# TDS_sensor.net
KiCad netlist of a schematic drawn in Altium Designer
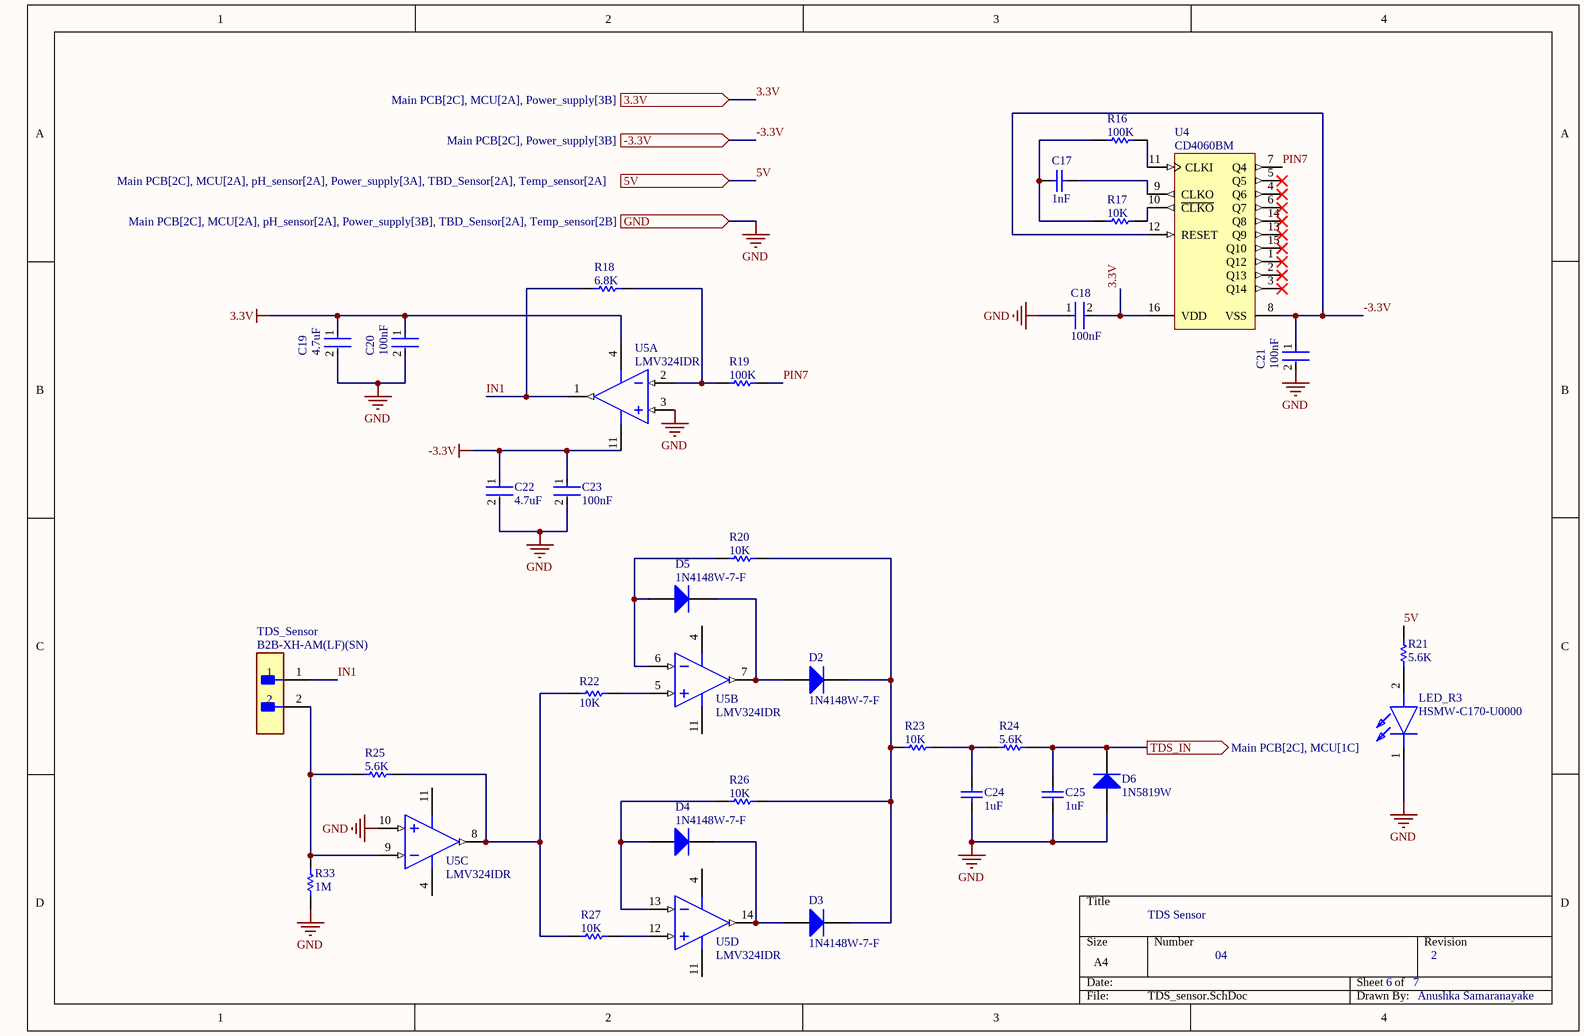
[diagram p0: TDS_sensor.SchDoc]

(export (version "E")
  (design (tool "Eeschema 10.0.6"))
  (components
    (comp (ref "C17")
      (value "1nF")
      (footprint "CAPC2013X135X50LL15T20")
      (fields (field (name "MANUFACTURER") "Vitramon") (field (name "PART NUMBER") "VJ0805Y102KXACW1BC"))
      (libsource (lib "Altium Content Vault") (part "CAP"))
    )
    (comp (ref "C18")
      (value "100nF")
      (footprint "FP-CL31-IPC_B")
      (description "Cap Ceramic 100nF 50V X7R ±10% SMD 1206 +125°C Embossed T/R")
      (fields (field (name "VOLTAGE") "50V") (field (name "TOLERANCE") "10%"))
      (libsource (lib "Altium Content Vault") (part "b4654b650e69147ec39a6b967a45e02"))
    )
    (comp (ref "C19")
      (value "4.7uF")
      (footprint "FP-CL31-IPC_B")
      (description "Cap Ceramic 100nF 50V X7R ±10% SMD 1206 +125°C Embossed T/R")
      (fields (field (name "VOLTAGE") "50V") (field (name "TOLERANCE") "10%"))
      (libsource (lib "Altium Content Vault") (part "b4654b650e69147ec39a6b967a45e02"))
    )
    (comp (ref "C20")
      (value "100nF")
      (footprint "FP-CL31-IPC_B")
      (description "Cap Ceramic 100nF 50V X7R ±10% SMD 1206 +125°C Embossed T/R")
      (fields (field (name "VOLTAGE") "50V") (field (name "TOLERANCE") "10%"))
      (libsource (lib "Altium Content Vault") (part "b4654b650e69147ec39a6b967a45e02"))
    )
    (comp (ref "C21")
      (value "100nF")
      (footprint "FP-CL31-IPC_B")
      (description "Cap Ceramic 100nF 50V X7R ±10% SMD 1206 +125°C Embossed T/R")
      (fields (field (name "VOLTAGE") "50V") (field (name "TOLERANCE") "10%"))
      (libsource (lib "Altium Content Vault") (part "b4654b650e69147ec39a6b967a45e02"))
    )
    (comp (ref "C22")
      (value "4.7uF")
      (footprint "FP-CL31-IPC_B")
      (description "Cap Ceramic 100nF 50V X7R ±10% SMD 1206 +125°C Embossed T/R")
      (fields (field (name "VOLTAGE") "50V") (field (name "TOLERANCE") "10%"))
      (libsource (lib "Altium Content Vault") (part "b4654b650e69147ec39a6b967a45e02"))
    )
    (comp (ref "C23")
      (value "100nF")
      (footprint "FP-CL31-IPC_B")
      (description "Cap Ceramic 100nF 50V X7R ±10% SMD 1206 +125°C Embossed T/R")
      (fields (field (name "VOLTAGE") "50V") (field (name "TOLERANCE") "10%"))
      (libsource (lib "Altium Content Vault") (part "b4654b650e69147ec39a6b967a45e02"))
    )
    (comp (ref "C24")
      (value "1uF")
      (footprint "CAPC2013X135X50LL15T20")
      (fields (field (name "MANUFACTURER") "Vitramon") (field (name "PART NUMBER") "VJ0805Y102KXACW1BC"))
      (libsource (lib "Altium Content Vault") (part "CAP"))
    )
    (comp (ref "C25")
      (value "1uF")
      (footprint "CAPC2013X135X50LL15T20")
      (fields (field (name "MANUFACTURER") "Vitramon") (field (name "PART NUMBER") "VJ0805Y102KXACW1BC"))
      (libsource (lib "Altium Content Vault") (part "CAP"))
    )
    (comp (ref "D2")
      (value "1N4148W-7-F")
      (footprint "DIOD-SOD123-2_V")
      (description "Fast Switching Diode, 100 V, 0.15 A, -65 to 150 degC, 2-Pin?SOD123, RoHS, Tape and Reel")
      (fields (field (name "MANUFACTURER") "DiodesIncorporated"))
      (libsource (lib "Altium Content Vault") (part "D-AK-2"))
    )
    (comp (ref "D3")
      (value "1N4148W-7-F")
      (footprint "DIOD-SOD123-2_V")
      (description "Fast Switching Diode, 100 V, 0.15 A, -65 to 150 degC, 2-Pin?SOD123, RoHS, Tape and Reel")
      (fields (field (name "MANUFACTURER") "DiodesIncorporated"))
      (libsource (lib "Altium Content Vault") (part "D-AK-2"))
    )
    (comp (ref "D4")
      (value "1N4148W-7-F")
      (footprint "DIOD-SOD123-2_V")
      (description "Fast Switching Diode, 100 V, 0.15 A, -65 to 150 degC, 2-Pin?SOD123, RoHS, Tape and Reel")
      (fields (field (name "MANUFACTURER") "DiodesIncorporated"))
      (libsource (lib "Altium Content Vault") (part "D-AK-2"))
    )
    (comp (ref "D5")
      (value "1N4148W-7-F")
      (footprint "DIOD-SOD123-2_V")
      (description "Fast Switching Diode, 100 V, 0.15 A, -65 to 150 degC, 2-Pin?SOD123, RoHS, Tape and Reel")
      (fields (field (name "MANUFACTURER") "DiodesIncorporated"))
      (libsource (lib "Altium Content Vault") (part "D-AK-2"))
    )
    (comp (ref "D6")
      (value "1N5819W")
      (footprint "DIOD-SOD123-2_V")
      (description "Fast Switching Diode, 100 V, 0.15 A, -65 to 150 degC, 2-Pin?SOD123, RoHS, Tape and Reel")
      (fields (field (name "MANUFACTURER") "DiodesIncorporated"))
      (libsource (lib "Altium Content Vault") (part "D-AK-2"))
    )
    (comp (ref "LED_R3")
      (value "HSMW-C170-U0000")
      (footprint "SamacSys:LEDC2012X90N")
      (description "LED")
      (fields (field (name "MOUSER PART NUMBER") "630-HSMW-C170-U0000"))
      (libsource (lib "*") (part "HSMW-C170-U0000"))
    )
    (comp (ref "R16")
      (value "100K")
      (footprint "RESC3216X70X50LL20T25")
      (fields (field (name "MANUFACTURER") "Panasonic") (field (name "PART NUMBER") "ERA8AEB103V"))
      (libsource (lib "Altium Content Vault") (part "RES"))
    )
    (comp (ref "R17")
      (value "10K")
      (footprint "RESC3216X70X50LL20T25")
      (fields (field (name "MANUFACTURER") "Panasonic") (field (name "PART NUMBER") "ERA8AEB103V"))
      (libsource (lib "Altium Content Vault") (part "RES"))
    )
    (comp (ref "R18")
      (value "6.8K")
      (footprint "RESC3216X70X50LL20T25")
      (fields (field (name "MANUFACTURER") "Panasonic") (field (name "PART NUMBER") "ERA8AEB103V"))
      (libsource (lib "Altium Content Vault") (part "RES"))
    )
    (comp (ref "R19")
      (value "100K")
      (footprint "RESC3216X70X50LL20T25")
      (fields (field (name "MANUFACTURER") "Panasonic") (field (name "PART NUMBER") "ERA8AEB103V"))
      (libsource (lib "Altium Content Vault") (part "RES"))
    )
    (comp (ref "R20")
      (value "10K")
      (footprint "RESC3216X70X50LL20T25")
      (fields (field (name "MANUFACTURER") "Panasonic") (field (name "PART NUMBER") "ERA8AEB103V"))
      (libsource (lib "Altium Content Vault") (part "RES"))
    )
    (comp (ref "R21")
      (value "5.6K")
      (footprint "RESC3216X70X50LL20T25")
      (fields (field (name "MANUFACTURER") "Panasonic") (field (name "PART NUMBER") "ERA8AEB103V"))
      (libsource (lib "Altium Content Vault") (part "RES"))
    )
    (comp (ref "R22")
      (value "10K")
      (footprint "RESC3216X70X50LL20T25")
      (fields (field (name "MANUFACTURER") "Panasonic") (field (name "PART NUMBER") "ERA8AEB103V"))
      (libsource (lib "Altium Content Vault") (part "RES"))
    )
    (comp (ref "R23")
      (value "10K")
      (footprint "RESC3216X70X50LL20T25")
      (fields (field (name "MANUFACTURER") "Panasonic") (field (name "PART NUMBER") "ERA8AEB103V"))
      (libsource (lib "Altium Content Vault") (part "RES"))
    )
    (comp (ref "R24")
      (value "5.6K")
      (footprint "RESC3216X70X50LL20T25")
      (fields (field (name "MANUFACTURER") "Panasonic") (field (name "PART NUMBER") "ERA8AEB103V"))
      (libsource (lib "Altium Content Vault") (part "RES"))
    )
    (comp (ref "R25")
      (value "5.6K")
      (footprint "RESC3216X70X50LL20T25")
      (fields (field (name "MANUFACTURER") "Panasonic") (field (name "PART NUMBER") "ERA8AEB103V"))
      (libsource (lib "Altium Content Vault") (part "RES"))
    )
    (comp (ref "R26")
      (value "10K")
      (footprint "RESC3216X70X50LL20T25")
      (fields (field (name "MANUFACTURER") "Panasonic") (field (name "PART NUMBER") "ERA8AEB103V"))
      (libsource (lib "Altium Content Vault") (part "RES"))
    )
    (comp (ref "R27")
      (value "10K")
      (footprint "RESC3216X70X50LL20T25")
      (fields (field (name "MANUFACTURER") "Panasonic") (field (name "PART NUMBER") "ERA8AEB103V"))
      (libsource (lib "Altium Content Vault") (part "RES"))
    )
    (comp (ref "R33")
      (value "1M")
      (footprint "RESC3216X70X50LL20T25")
      (fields (field (name "MANUFACTURER") "Panasonic") (field (name "PART NUMBER") "ERA8AEB103V"))
      (libsource (lib "Altium Content Vault") (part "RES"))
    )
    (comp (ref "TDS_Sensor")
      (value "B2B-XH-AM(LF)(SN)")
      (footprint "FP-B2B-XH-AM_LF_SN-MFG")
      (description "CONN HEADER VERT 2POS 2.5MM")
      (libsource (lib "Altium Content Vault") (part "3bc925449376181038e59eaffc5286c"))
    )
    (comp (ref "U4")
      (value "CD4060BM")
      (footprint "D0016A_M")
      (fields (field (name "MANUFACTURER") "Texas Instruments"))
      (libsource (lib "Altium Content Vault") (part "TI-CD4060B-16"))
    )
    (comp (ref "U5")
      (value "LMV324IDR")
      (footprint "D0014A_V")
      (libsource (lib "Altium Content Vault") (part "TI-LMV324-D-14"))
    )
  )
  (nets
    (net (code "1") (name "-3.3V") (class "Default")
      (node (ref "C21") (pin "1") (pinfunction "1_1") (pintype "passive"))
      (node (ref "C22") (pin "1") (pinfunction "1_1") (pintype "passive"))
      (node (ref "C23") (pin "1") (pinfunction "1_1") (pintype "passive"))
      (node (ref "U4") (pin "12") (pinfunction "RESET_12") (pintype "input"))
      (node (ref "U4") (pin "8") (pinfunction "VSS_8") (pintype "passive"))
      (node (ref "U5") (pin "11") (pinfunction "GND_11") (pintype "power_in"))
    )
    (net (code "2") (name "/5V") (class "Default")
      (node (ref "R21") (pin "1") (pinfunction "1_1") (pintype "passive"))
    )
    (net (code "3") (name "/IN1") (class "Default")
      (node (ref "R18") (pin "2") (pinfunction "2_2") (pintype "passive"))
      (node (ref "TDS_Sensor") (pin "1") (pinfunction "1_1") (pintype "passive"))
      (node (ref "U5") (pin "1") (pinfunction "1OUT_1") (pintype "output"))
    )
    (net (code "4") (name "/PIN7") (class "Default")
      (node (ref "R19") (pin "1") (pinfunction "1_1") (pintype "passive"))
      (node (ref "U4") (pin "7") (pinfunction "Q4_7") (pintype "output"))
    )
    (net (code "5") (name "/TDS_IN") (class "Default")
      (node (ref "C25") (pin "2") (pinfunction "2_2") (pintype "passive"))
      (node (ref "D6") (pin "2") (pinfunction "K_2") (pintype "passive"))
      (node (ref "R24") (pin "1") (pinfunction "1_1") (pintype "passive"))
    )
    (net (code "6") (name "3.3V") (class "Default")
      (node (ref "C18") (pin "2") (pinfunction "2_2") (pintype "passive"))
      (node (ref "C19") (pin "1") (pinfunction "1_1") (pintype "passive"))
      (node (ref "C20") (pin "1") (pinfunction "1_1") (pintype "passive"))
      (node (ref "U4") (pin "16") (pinfunction "VDD_16") (pintype "passive"))
      (node (ref "U5") (pin "4") (pinfunction "VCC+_4") (pintype "power_in"))
    )
    (net (code "7") (name "GND") (class "Default")
      (node (ref "C18") (pin "1") (pinfunction "1_1") (pintype "passive"))
      (node (ref "C19") (pin "2") (pinfunction "2_2") (pintype "passive"))
      (node (ref "C20") (pin "2") (pinfunction "2_2") (pintype "passive"))
      (node (ref "C21") (pin "2") (pinfunction "2_2") (pintype "passive"))
      (node (ref "C22") (pin "2") (pinfunction "2_2") (pintype "passive"))
      (node (ref "C23") (pin "2") (pinfunction "2_2") (pintype "passive"))
      (node (ref "C24") (pin "1") (pinfunction "1_1") (pintype "passive"))
      (node (ref "C25") (pin "1") (pinfunction "1_1") (pintype "passive"))
      (node (ref "D6") (pin "1") (pinfunction "A_1") (pintype "passive"))
      (node (ref "LED_R3") (pin "1") (pinfunction "K_1") (pintype "passive"))
      (node (ref "R33") (pin "2") (pinfunction "2_2") (pintype "passive"))
      (node (ref "U5") (pin "10") (pinfunction "3IN+_10") (pintype "input"))
      (node (ref "U5") (pin "3") (pinfunction "1IN+_3") (pintype "input"))
    )
    (net (code "8") (name "Net-(C17-Pad1)") (class "Default")
      (node (ref "C17") (pin "1") (pinfunction "1_1") (pintype "passive"))
      (node (ref "R16") (pin "2") (pinfunction "2_2") (pintype "passive"))
      (node (ref "R17") (pin "2") (pinfunction "2_2") (pintype "passive"))
    )
    (net (code "9") (name "Net-(C24-Pad2)") (class "Default")
      (node (ref "C24") (pin "2") (pinfunction "2_2") (pintype "passive"))
      (node (ref "R23") (pin "1") (pinfunction "1_1") (pintype "passive"))
      (node (ref "R24") (pin "2") (pinfunction "2_2") (pintype "passive"))
    )
    (net (code "10") (name "Net-(D2-A)") (class "Default")
      (node (ref "D2") (pin "1") (pinfunction "A_1") (pintype "passive"))
      (node (ref "D5") (pin "2") (pinfunction "K_2") (pintype "passive"))
      (node (ref "U5") (pin "7") (pinfunction "2OUT_7") (pintype "output"))
    )
    (net (code "11") (name "Net-(D2-K)") (class "Default")
      (node (ref "D2") (pin "2") (pinfunction "K_2") (pintype "passive"))
      (node (ref "D3") (pin "2") (pinfunction "K_2") (pintype "passive"))
      (node (ref "R20") (pin "1") (pinfunction "1_1") (pintype "passive"))
      (node (ref "R23") (pin "2") (pinfunction "2_2") (pintype "passive"))
      (node (ref "R26") (pin "1") (pinfunction "1_1") (pintype "passive"))
    )
    (net (code "12") (name "Net-(D3-A)") (class "Default")
      (node (ref "D3") (pin "1") (pinfunction "A_1") (pintype "passive"))
      (node (ref "D4") (pin "2") (pinfunction "K_2") (pintype "passive"))
      (node (ref "U5") (pin "14") (pinfunction "4OUT_14") (pintype "output"))
    )
    (net (code "13") (name "Net-(D4-A)") (class "Default")
      (node (ref "D4") (pin "1") (pinfunction "A_1") (pintype "passive"))
      (node (ref "R26") (pin "2") (pinfunction "2_2") (pintype "passive"))
      (node (ref "U5") (pin "13") (pinfunction "4IN-_13") (pintype "input"))
    )
    (net (code "14") (name "Net-(D5-A)") (class "Default")
      (node (ref "D5") (pin "1") (pinfunction "A_1") (pintype "passive"))
      (node (ref "R20") (pin "2") (pinfunction "2_2") (pintype "passive"))
      (node (ref "U5") (pin "6") (pinfunction "2IN-_6") (pintype "input"))
    )
    (net (code "15") (name "Net-(LED_R3-A)") (class "Default")
      (node (ref "LED_R3") (pin "2") (pinfunction "A_2") (pintype "passive"))
      (node (ref "R21") (pin "2") (pinfunction "2_2") (pintype "passive"))
    )
    (net (code "16") (name "Net-(U4-CLKI)") (class "Default")
      (node (ref "R16") (pin "1") (pinfunction "1_1") (pintype "passive"))
      (node (ref "U4") (pin "11") (pinfunction "CLKI_11") (pintype "input"))
    )
    (net (code "17") (name "Net-(U4-CLKO)") (class "Default")
      (node (ref "C17") (pin "2") (pinfunction "2_2") (pintype "passive"))
      (node (ref "U4") (pin "9") (pinfunction "CLKO_9") (pintype "output"))
    )
    (net (code "18") (name "Net-(U4-~{CLKO})") (class "Default")
      (node (ref "R17") (pin "1") (pinfunction "1_1") (pintype "passive"))
      (node (ref "U4") (pin "10") (pinfunction "~{CLKO}_10") (pintype "output"))
    )
    (net (code "19") (name "Net-(U5A-1IN-)") (class "Default")
      (node (ref "R18") (pin "1") (pinfunction "1_1") (pintype "passive"))
      (node (ref "R19") (pin "2") (pinfunction "2_2") (pintype "passive"))
      (node (ref "U5") (pin "2") (pinfunction "1IN-_2") (pintype "input"))
    )
    (net (code "20") (name "Net-(U5B-2IN+)") (class "Default")
      (node (ref "R22") (pin "1") (pinfunction "1_1") (pintype "passive"))
      (node (ref "U5") (pin "5") (pinfunction "2IN+_5") (pintype "input"))
    )
    (net (code "21") (name "Net-(U5C-3IN-)") (class "Default")
      (node (ref "R25") (pin "2") (pinfunction "2_2") (pintype "passive"))
      (node (ref "R33") (pin "1") (pinfunction "1_1") (pintype "passive"))
      (node (ref "TDS_Sensor") (pin "2") (pinfunction "2_2") (pintype "passive"))
      (node (ref "U5") (pin "9") (pinfunction "3IN-_9") (pintype "input"))
    )
    (net (code "22") (name "Net-(U5C-3OUT)") (class "Default")
      (node (ref "R22") (pin "2") (pinfunction "2_2") (pintype "passive"))
      (node (ref "R25") (pin "1") (pinfunction "1_1") (pintype "passive"))
      (node (ref "R27") (pin "2") (pinfunction "2_2") (pintype "passive"))
      (node (ref "U5") (pin "8") (pinfunction "3OUT_8") (pintype "output"))
    )
    (net (code "23") (name "Net-(U5D-4IN+)") (class "Default")
      (node (ref "R27") (pin "1") (pinfunction "1_1") (pintype "passive"))
      (node (ref "U5") (pin "12") (pinfunction "4IN+_12") (pintype "input"))
    )
    (net (code "24") (name "unconnected-(U4-Q5-Pad5)") (class "Default")
      (node (ref "U4") (pin "5") (pinfunction "Q5_5") (pintype "output+no_connect"))
    )
    (net (code "25") (name "unconnected-(U4-Q6-Pad4)") (class "Default")
      (node (ref "U4") (pin "4") (pinfunction "Q6_4") (pintype "output+no_connect"))
    )
    (net (code "26") (name "unconnected-(U4-Q7-Pad6)") (class "Default")
      (node (ref "U4") (pin "6") (pinfunction "Q7_6") (pintype "output+no_connect"))
    )
    (net (code "27") (name "unconnected-(U4-Q8-Pad14)") (class "Default")
      (node (ref "U4") (pin "14") (pinfunction "Q8_14") (pintype "output+no_connect"))
    )
    (net (code "28") (name "unconnected-(U4-Q9-Pad13)") (class "Default")
      (node (ref "U4") (pin "13") (pinfunction "Q9_13") (pintype "output+no_connect"))
    )
    (net (code "29") (name "unconnected-(U4-Q10-Pad15)") (class "Default")
      (node (ref "U4") (pin "15") (pinfunction "Q10_15") (pintype "output+no_connect"))
    )
    (net (code "30") (name "unconnected-(U4-Q12-Pad1)") (class "Default")
      (node (ref "U4") (pin "1") (pinfunction "Q12_1") (pintype "output+no_connect"))
    )
    (net (code "31") (name "unconnected-(U4-Q13-Pad2)") (class "Default")
      (node (ref "U4") (pin "2") (pinfunction "Q13_2") (pintype "output+no_connect"))
    )
    (net (code "32") (name "unconnected-(U4-Q14-Pad3)") (class "Default")
      (node (ref "U4") (pin "3") (pinfunction "Q14_3") (pintype "output+no_connect"))
    )
    (net (code "33") (name "unconnected-(U5B-GND-Pad11)") (class "Default")
      (node (ref "U5") (pin "11") (pinfunction "GND_11") (pintype "power_in"))
    )
    (net (code "34") (name "unconnected-(U5B-VCC+-Pad4)") (class "Default")
      (node (ref "U5") (pin "4") (pinfunction "VCC+_4") (pintype "power_in"))
    )
    (net (code "35") (name "unconnected-(U5C-GND-Pad11)") (class "Default")
      (node (ref "U5") (pin "11") (pinfunction "GND_11") (pintype "power_in"))
    )
    (net (code "36") (name "unconnected-(U5C-VCC+-Pad4)") (class "Default")
      (node (ref "U5") (pin "4") (pinfunction "VCC+_4") (pintype "power_in"))
    )
    (net (code "37") (name "unconnected-(U5D-GND-Pad11)") (class "Default")
      (node (ref "U5") (pin "11") (pinfunction "GND_11") (pintype "power_in"))
    )
    (net (code "38") (name "unconnected-(U5D-VCC+-Pad4)") (class "Default")
      (node (ref "U5") (pin "4") (pinfunction "VCC+_4") (pintype "power_in"))
    )
  )
)
